# Touch_panel.net
KiCad netlist of a schematic drawn in Altium Designer
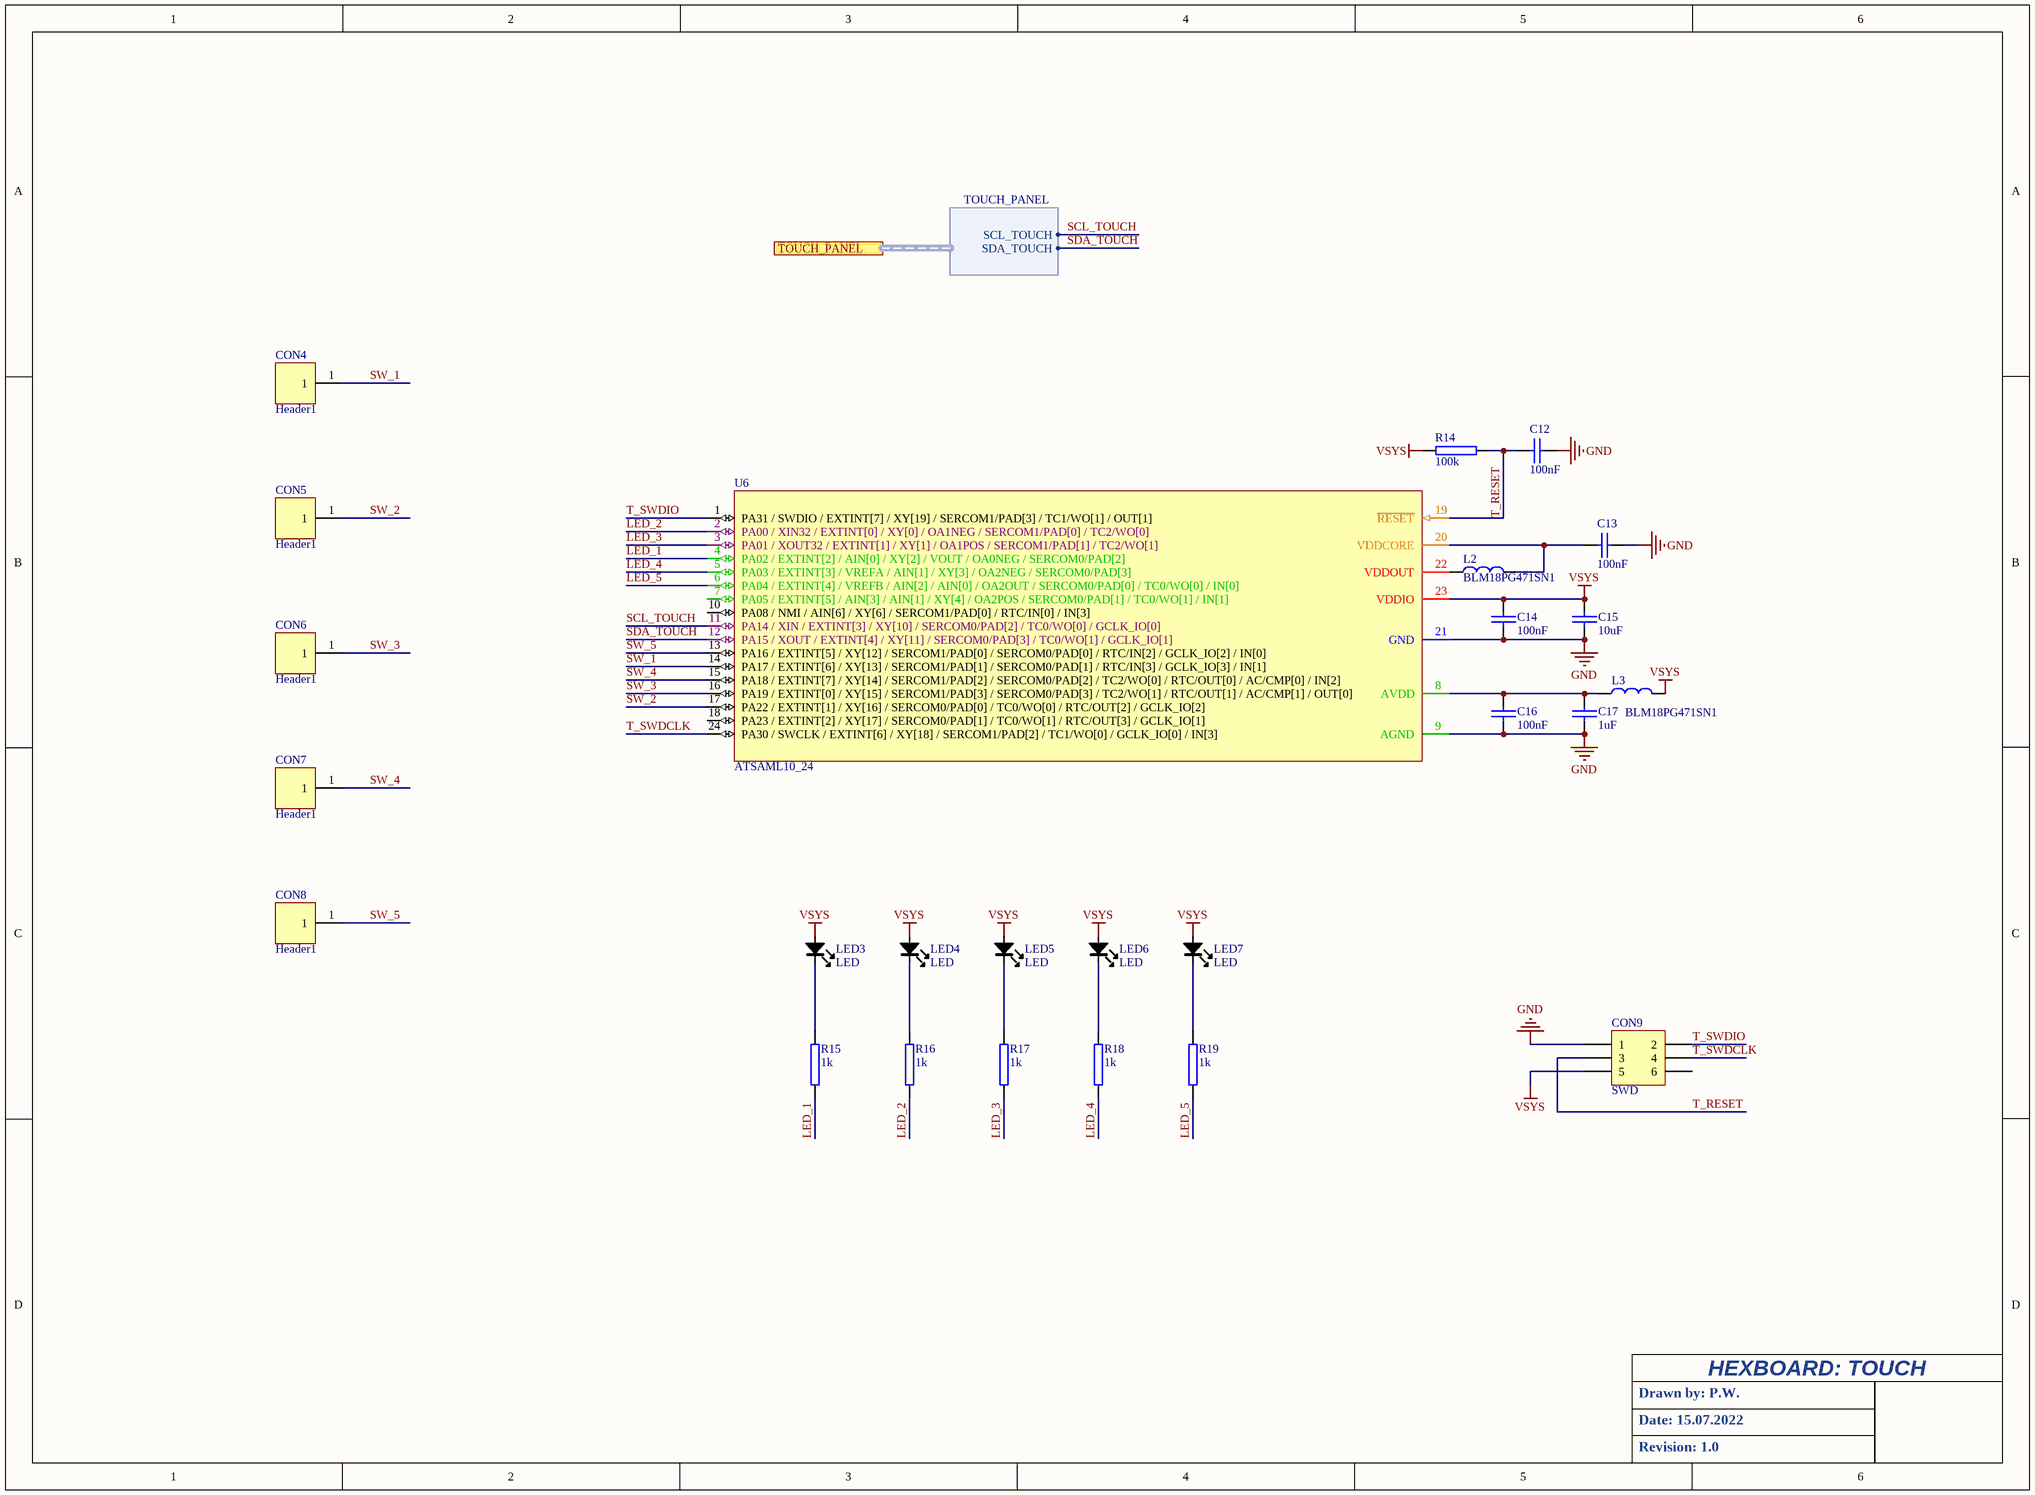
[diagram p0: Touch_panel.SchDoc]

(export (version "E")
  (design (tool "Eeschema 10.0.6"))
  (components
    (comp (ref "C12")
      (value "100nF")
      (footprint "C0603L")
      (description "Capacitor")
      (libsource (lib "LIB_PW") (part "CAP"))
    )
    (comp (ref "C13")
      (value "100nF")
      (footprint "C0603L")
      (description "Capacitor")
      (libsource (lib "LIB_PW") (part "CAP"))
    )
    (comp (ref "C14")
      (value "100nF")
      (footprint "C0603L")
      (description "Capacitor")
      (libsource (lib "LIB_PW") (part "CAP"))
    )
    (comp (ref "C15")
      (value "10uF")
      (footprint "C0603L")
      (description "Capacitor")
      (libsource (lib "LIB_PW") (part "CAP"))
    )
    (comp (ref "C16")
      (value "100nF")
      (footprint "C0603L")
      (description "Capacitor")
      (libsource (lib "LIB_PW") (part "CAP"))
    )
    (comp (ref "C17")
      (value "1uF")
      (footprint "C0603L")
      (description "Capacitor")
      (libsource (lib "LIB_PW") (part "CAP"))
    )
    (comp (ref "CON4")
      (value "Header1")
      (footprint "P_CAP_13mm_B")
      (libsource (lib "LIB_PW") (part "Header1"))
    )
    (comp (ref "CON5")
      (value "Header1")
      (footprint "P_CAP_13mm_B")
      (libsource (lib "LIB_PW") (part "Header1"))
    )
    (comp (ref "CON6")
      (value "Header1")
      (footprint "P_CAP_13mm_B")
      (libsource (lib "LIB_PW") (part "Header1"))
    )
    (comp (ref "CON7")
      (value "Header1")
      (footprint "P_CAP_13mm_B")
      (libsource (lib "LIB_PW") (part "Header1"))
    )
    (comp (ref "CON8")
      (value "Header1")
      (footprint "P_CAP_13mm_B")
      (libsource (lib "LIB_PW") (part "Header1"))
    )
    (comp (ref "CON9")
      (value "SWD")
      (footprint "HDR2x3_1mm27")
      (description "Header, 3-Pin, Dual row")
      (fields (field (name "PUBLISHER") "Altium Limited"))
      (libsource (lib "LIB_PW") (part "Header 3X2"))
    )
    (comp (ref "L2") (value "BLM18PG471SN1") (footprint "L0805") (libsource (lib "LIB_PW") (part "INDUCTOR")))
    (comp (ref "L3") (value "BLM18PG471SN1") (footprint "L0805") (libsource (lib "LIB_PW") (part "INDUCTOR")))
    (comp (ref "LED3") (value "LED") (footprint "LED1206_BOTTOM_2_5") (libsource (lib "LIB_PW") (part "LED")))
    (comp (ref "LED4") (value "LED") (footprint "LED1206_BOTTOM_2_5") (libsource (lib "LIB_PW") (part "LED")))
    (comp (ref "LED5") (value "LED") (footprint "LED1206_BOTTOM_2_5") (libsource (lib "LIB_PW") (part "LED")))
    (comp (ref "LED6") (value "LED") (footprint "LED1206_BOTTOM_2_5") (libsource (lib "LIB_PW") (part "LED")))
    (comp (ref "LED7") (value "LED") (footprint "LED1206_BOTTOM_2_5") (libsource (lib "LIB_PW") (part "LED")))
    (comp (ref "R14") (value "100k") (footprint "1608[0603]") (libsource (lib "LIB_PW") (part "RES")))
    (comp (ref "R15") (value "1k") (footprint "1608[0603]") (libsource (lib "LIB_PW") (part "RES")))
    (comp (ref "R16") (value "1k") (footprint "1608[0603]") (libsource (lib "LIB_PW") (part "RES")))
    (comp (ref "R17") (value "1k") (footprint "1608[0603]") (libsource (lib "LIB_PW") (part "RES")))
    (comp (ref "R18") (value "1k") (footprint "1608[0603]") (libsource (lib "LIB_PW") (part "RES")))
    (comp (ref "R19") (value "1k") (footprint "1608[0603]") (libsource (lib "LIB_PW") (part "RES")))
    (comp (ref "U6")
      (value "ATSAML10_24")
      (footprint "QFN24_4x4")
      (description "Cortex M0+ microcontroller")
      (libsource (lib "LIB_PW") (part "ATSAML10D15"))
    )
  )
  (nets
    (net (code "2") (name "/LED_1") (class "Default")
      (node (ref "R15") (pin "1") (pinfunction "1_1") (pintype "passive"))
      (node (ref "U6") (pin "4") (pinfunction "PA02_/_EXTINT[2]_/_AIN[0]_/_XY[2]_/_VOUT_/_OA0NEG_/_SERCOM0/PAD[2]_4") (pintype "bidirectional"))
    )
    (net (code "3") (name "/LED_2") (class "Default")
      (node (ref "R16") (pin "2") (pinfunction "2_2") (pintype "passive"))
      (node (ref "U6") (pin "2") (pinfunction "PA00_/_XIN32_/_EXTINT[0]_/_XY[0]_/_OA1NEG_/_SERCOM1/PAD[0]_/_TC2/WO[0]_2") (pintype "bidirectional"))
    )
    (net (code "4") (name "/LED_3") (class "Default")
      (node (ref "R17") (pin "1") (pinfunction "1_1") (pintype "passive"))
      (node (ref "U6") (pin "3") (pinfunction "PA01_/_XOUT32_/_EXTINT[1]_/_XY[1]_/_OA1POS_/_SERCOM1/PAD[1]_/_TC2/WO[1]_3") (pintype "bidirectional"))
    )
    (net (code "5") (name "/LED_4") (class "Default")
      (node (ref "R18") (pin "1") (pinfunction "1_1") (pintype "passive"))
      (node (ref "U6") (pin "5") (pinfunction "PA03_/_EXTINT[3]_/_VREFA_/_AIN[1]_/_XY[3]_/_OA2NEG_/_SERCOM0/PAD[3]_5") (pintype "bidirectional"))
    )
    (net (code "6") (name "/LED_5") (class "Default")
      (node (ref "R19") (pin "2") (pinfunction "2_2") (pintype "passive"))
      (node (ref "U6") (pin "6") (pinfunction "PA04_/_EXTINT[4]_/_VREFB_/_AIN[2]_/_AIN[0]_/_OA2OUT_/_SERCOM0/PAD[0]_/_TC0/WO[0]_/_IN[0]_6") (pintype "bidirectional"))
    )
    (net (code "7") (name "/SCL_TOUCH") (class "Default")
      (node (ref "U6") (pin "11") (pinfunction "PA14_/_XIN_/_EXTINT[3]_/_XY[10]_/_SERCOM0/PAD[2]_/_TC0/WO[0]_/_GCLK_IO[0]_11") (pintype "bidirectional"))
    )
    (net (code "8") (name "/SDA_TOUCH") (class "Default")
      (node (ref "U6") (pin "12") (pinfunction "PA15_/_XOUT_/_EXTINT[4]_/_XY[11]_/_SERCOM0/PAD[3]_/_TC0/WO[1]_/_GCLK_IO[1]_12") (pintype "bidirectional"))
    )
    (net (code "9") (name "/SW_1") (class "Default")
      (node (ref "CON4") (pin "1") (pinfunction "1_1") (pintype "passive"))
      (node (ref "U6") (pin "14") (pinfunction "PA17_/_EXTINT[6]_/_XY[13]_/_SERCOM1/PAD[1]_/_SERCOM0/PAD[1]_/_RTC/IN[3]_/_GCLK_IO[3]_/_IN[1]_14") (pintype "bidirectional"))
    )
    (net (code "10") (name "/SW_2") (class "Default")
      (node (ref "CON5") (pin "1") (pinfunction "1_1") (pintype "passive"))
      (node (ref "U6") (pin "17") (pinfunction "PA22_/_EXTINT[1]_/_XY[16]_/_SERCOM0/PAD[0]_/_TC0/WO[0]_/_RTC/OUT[2]_/_GCLK_IO[2]_17") (pintype "bidirectional"))
    )
    (net (code "11") (name "/SW_3") (class "Default")
      (node (ref "CON6") (pin "1") (pinfunction "1_1") (pintype "passive"))
      (node (ref "U6") (pin "16") (pinfunction "PA19_/_EXTINT[0]_/_XY[15]_/_SERCOM1/PAD[3]_/_SERCOM0/PAD[3]_/_TC2/WO[1]_/_RTC/OUT[1]_/_AC/CMP[1]_/_OUT[0]_16") (pintype "bidirectional"))
    )
    (net (code "12") (name "/SW_4") (class "Default")
      (node (ref "CON7") (pin "1") (pinfunction "1_1") (pintype "passive"))
      (node (ref "U6") (pin "15") (pinfunction "PA18_/_EXTINT[7]_/_XY[14]_/_SERCOM1/PAD[2]_/_SERCOM0/PAD[2]_/_TC2/WO[0]_/_RTC/OUT[0]_/_AC/CMP[0]_/_IN[2]_15") (pintype "bidirectional"))
    )
    (net (code "13") (name "/SW_5") (class "Default")
      (node (ref "CON8") (pin "1") (pinfunction "1_1") (pintype "passive"))
      (node (ref "U6") (pin "13") (pinfunction "PA16_/_EXTINT[5]_/_XY[12]_/_SERCOM1/PAD[0]_/_SERCOM0/PAD[0]_/_RTC/IN[2]_/_GCLK_IO[2]_/_IN[0]_13") (pintype "bidirectional"))
    )
    (net (code "14") (name "/T_RESET") (class "Default")
      (node (ref "C12") (pin "1") (pinfunction "1_1") (pintype "passive"))
      (node (ref "CON9") (pin "3") (pinfunction "3_3") (pintype "passive"))
      (node (ref "R14") (pin "2") (pinfunction "2_2") (pintype "passive"))
      (node (ref "U6") (pin "19") (pinfunction "~{RESET}_19") (pintype "input"))
    )
    (net (code "15") (name "/T_SWDCLK") (class "Default")
      (node (ref "CON9") (pin "4") (pinfunction "4_4") (pintype "passive"))
      (node (ref "U6") (pin "24") (pinfunction "PA30_/_SWCLK_/_EXTINT[6]_/_XY[18]_/_SERCOM1/PAD[2]_/_TC1/WO[0]_/_GCLK_IO[0]_/_IN[3]_24") (pintype "bidirectional"))
    )
    (net (code "16") (name "/T_SWDIO") (class "Default")
      (node (ref "CON9") (pin "2") (pinfunction "2_2") (pintype "passive"))
      (node (ref "U6") (pin "1") (pinfunction "PA31_/_SWDIO_/_EXTINT[7]_/_XY[19]_/_SERCOM1/PAD[3]_/_TC1/WO[1]_/_OUT[1]_1") (pintype "bidirectional"))
    )
    (net (code "18") (name "GND") (class "Default")
      (node (ref "C12") (pin "2") (pinfunction "2_2") (pintype "passive"))
      (node (ref "C13") (pin "2") (pinfunction "2_2") (pintype "passive"))
      (node (ref "C14") (pin "2") (pinfunction "2_2") (pintype "passive"))
      (node (ref "C15") (pin "2") (pinfunction "2_2") (pintype "passive"))
      (node (ref "C16") (pin "2") (pinfunction "2_2") (pintype "passive"))
      (node (ref "C17") (pin "2") (pinfunction "2_2") (pintype "passive"))
      (node (ref "CON9") (pin "1") (pinfunction "1_1") (pintype "passive"))
      (node (ref "U6") (pin "21") (pinfunction "GND_21") (pintype "power_in"))
      (node (ref "U6") (pin "9") (pinfunction "AGND_9") (pintype "power_in"))
    )
    (net (code "19") (name "Net-(LED3-K)") (class "Default")
      (node (ref "LED3") (pin "2") (pinfunction "K_2") (pintype "passive"))
      (node (ref "R15") (pin "2") (pinfunction "2_2") (pintype "passive"))
    )
    (net (code "20") (name "Net-(LED4-K)") (class "Default")
      (node (ref "LED4") (pin "2") (pinfunction "K_2") (pintype "passive"))
      (node (ref "R16") (pin "1") (pinfunction "1_1") (pintype "passive"))
    )
    (net (code "21") (name "Net-(LED5-K)") (class "Default")
      (node (ref "LED5") (pin "2") (pinfunction "K_2") (pintype "passive"))
      (node (ref "R17") (pin "2") (pinfunction "2_2") (pintype "passive"))
    )
    (net (code "22") (name "Net-(LED6-K)") (class "Default")
      (node (ref "LED6") (pin "2") (pinfunction "K_2") (pintype "passive"))
      (node (ref "R18") (pin "2") (pinfunction "2_2") (pintype "passive"))
    )
    (net (code "23") (name "Net-(LED7-K)") (class "Default")
      (node (ref "LED7") (pin "2") (pinfunction "K_2") (pintype "passive"))
      (node (ref "R19") (pin "1") (pinfunction "1_1") (pintype "passive"))
    )
    (net (code "24") (name "Net-(U6-AVDD)") (class "Default")
      (node (ref "C16") (pin "1") (pinfunction "1_1") (pintype "passive"))
      (node (ref "C17") (pin "1") (pinfunction "1_1") (pintype "passive"))
      (node (ref "L3") (pin "1") (pinfunction "1_1") (pintype "passive"))
      (node (ref "U6") (pin "8") (pinfunction "AVDD_8") (pintype "power_in"))
    )
    (net (code "25") (name "Net-(U6-VDDCORE)") (class "Default")
      (node (ref "C13") (pin "1") (pinfunction "1_1") (pintype "passive"))
      (node (ref "L2") (pin "2") (pinfunction "2_2") (pintype "passive"))
      (node (ref "U6") (pin "20") (pinfunction "VDDCORE_20") (pintype "power_in"))
    )
    (net (code "26") (name "Net-(U6-VDDOUT)") (class "Default")
      (node (ref "L2") (pin "1") (pinfunction "1_1") (pintype "passive"))
      (node (ref "U6") (pin "22") (pinfunction "VDDOUT_22") (pintype "power_in"))
    )
    (net (code "27") (name "VSYS") (class "Default")
      (node (ref "C14") (pin "1") (pinfunction "1_1") (pintype "passive"))
      (node (ref "C15") (pin "1") (pinfunction "1_1") (pintype "passive"))
      (node (ref "CON9") (pin "5") (pinfunction "5_5") (pintype "passive"))
      (node (ref "L3") (pin "2") (pinfunction "2_2") (pintype "passive"))
      (node (ref "LED3") (pin "1") (pinfunction "A_1") (pintype "passive"))
      (node (ref "LED4") (pin "1") (pinfunction "A_1") (pintype "passive"))
      (node (ref "LED5") (pin "1") (pinfunction "A_1") (pintype "passive"))
      (node (ref "LED6") (pin "1") (pinfunction "A_1") (pintype "passive"))
      (node (ref "LED7") (pin "1") (pinfunction "A_1") (pintype "passive"))
      (node (ref "R14") (pin "1") (pinfunction "1_1") (pintype "passive"))
      (node (ref "U6") (pin "23") (pinfunction "VDDIO_23") (pintype "power_in"))
    )
    (net (code "28") (name "unconnected-(CON9-Pad6)") (class "Default")
      (node (ref "CON9") (pin "6") (pinfunction "6_6") (pintype "passive"))
    )
    (net (code "29") (name "unconnected-(U6-PA05_{slash}_EXTINT[5]_{slash}_AIN[3]_{slash}_AIN[1]_{slash}_XY[4]_{slash}_OA2POS_{slash}_SERCOM0{slash}PAD[1]_{slash}_TC0{slash}WO[1]_{slash}_IN[1]-Pad7)") (class "Default")
      (node (ref "U6") (pin "7") (pinfunction "PA05_/_EXTINT[5]_/_AIN[3]_/_AIN[1]_/_XY[4]_/_OA2POS_/_SERCOM0/PAD[1]_/_TC0/WO[1]_/_IN[1]_7") (pintype "bidirectional"))
    )
    (net (code "30") (name "unconnected-(U6-PA08_{slash}_NMI_{slash}_AIN[6]_{slash}_XY[6]_{slash}_SERCOM1{slash}PAD[0]_{slash}_RTC{slash}IN[0]_{slash}_IN[3]-Pad10)") (class "Default")
      (node (ref "U6") (pin "10") (pinfunction "PA08_/_NMI_/_AIN[6]_/_XY[6]_/_SERCOM1/PAD[0]_/_RTC/IN[0]_/_IN[3]_10") (pintype "bidirectional"))
    )
    (net (code "31") (name "unconnected-(U6-PA23_{slash}_EXTINT[2]_{slash}_XY[17]_{slash}_SERCOM0{slash}PAD[1]_{slash}_TC0{slash}WO[1]_{slash}_RTC{slash}OUT[3]_{slash}_GCLK_IO[1]-Pad18)") (class "Default")
      (node (ref "U6") (pin "18") (pinfunction "PA23_/_EXTINT[2]_/_XY[17]_/_SERCOM0/PAD[1]_/_TC0/WO[1]_/_RTC/OUT[3]_/_GCLK_IO[1]_18") (pintype "bidirectional"))
    )
  )
)
